# c_Single_Switch_QBC.net
KiCad netlist of a schematic drawn in EAGLE
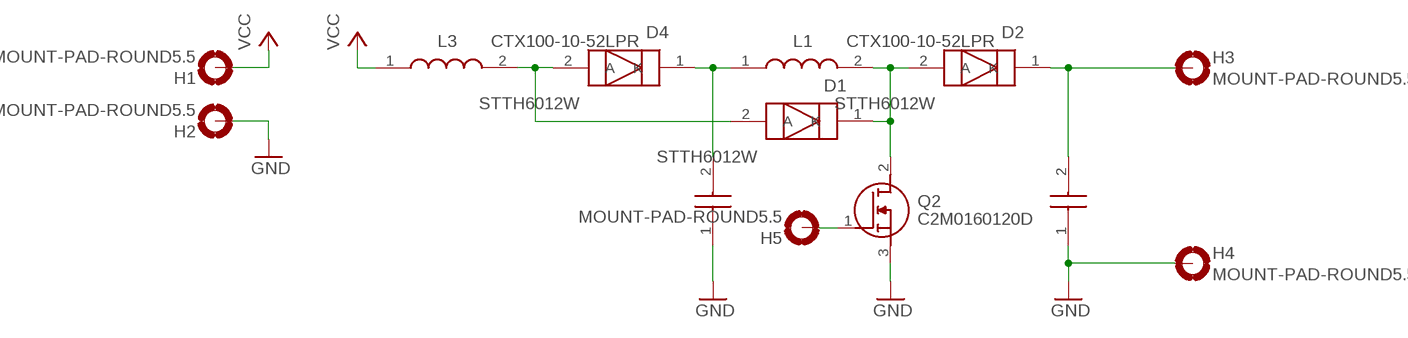
[diagram p0: schematic, sheet 1]

(export (version "E")
  (design (tool "Eeschema 10.0.6"))
  (components
    (comp (ref "D1")
      (value "STTH6012W")
      (footprint "eagle-import:TO1090P515X1560X2445-2P")
      (fields (field (name "RS_PART_NUMBER") "6870818"))
      (libsource (lib "eagle-import") (part "STTH6012W"))
    )
    (comp (ref "D2")
      (value "STTH6012W")
      (footprint "eagle-import:TO1090P515X1560X2445-2P")
      (fields (field (name "RS_PART_NUMBER") "6870818"))
      (libsource (lib "eagle-import") (part "STTH6012W"))
    )
    (comp (ref "D4")
      (value "STTH6012W")
      (footprint "eagle-import:TO1090P515X1560X2445-2P")
      (fields (field (name "RS_PART_NUMBER") "6870818"))
      (libsource (lib "eagle-import") (part "STTH6012W"))
    )
    (comp (ref "H1")
      (value "MOUNT-PAD-ROUND5.5")
      (footprint "eagle-import:5,5-PAD")
      (libsource (lib "eagle-import") (part "MOUNT-PAD-ROUND5.5"))
    )
    (comp (ref "H2")
      (value "MOUNT-PAD-ROUND5.5")
      (footprint "eagle-import:5,5-PAD")
      (libsource (lib "eagle-import") (part "MOUNT-PAD-ROUND5.5"))
    )
    (comp (ref "H3")
      (value "MOUNT-PAD-ROUND5.5")
      (footprint "eagle-import:5,5-PAD")
      (libsource (lib "eagle-import") (part "MOUNT-PAD-ROUND5.5"))
    )
    (comp (ref "H4")
      (value "MOUNT-PAD-ROUND5.5")
      (footprint "eagle-import:5,5-PAD")
      (libsource (lib "eagle-import") (part "MOUNT-PAD-ROUND5.5"))
    )
    (comp (ref "H5")
      (value "MOUNT-PAD-ROUND5.5")
      (footprint "eagle-import:5,5-PAD")
      (libsource (lib "eagle-import") (part "MOUNT-PAD-ROUND5.5"))
    )
    (comp (ref "L1")
      (value "CTX100-10-52LPR")
      (footprint "eagle-import:CTX1001052LPR")
      (libsource (lib "eagle-import") (part "CTX100-10-52LPR"))
    )
    (comp (ref "L3")
      (value "CTX100-10-52LPR")
      (footprint "eagle-import:CTX1001052LPR")
      (libsource (lib "eagle-import") (part "CTX100-10-52LPR"))
    )
    (comp (ref "Q2")
      (value "C2M0160120D")
      (footprint "eagle-import:TO544P521X1594X2550-3P")
      (fields (field (name "RS_PART_NUMBER") "1629709"))
      (libsource (lib "eagle-import") (part "C2M0160120D"))
    )
    (comp (ref "U$1")
      (value "B32774D4505K000")
      (footprint "eagle-import:B32774D4505K000")
      (fields (field (name "RS_PART_NUMBER") "1726009"))
      (libsource (lib "eagle-import") (part "B32774D4505K000"))
    )
    (comp (ref "U$2")
      (value "B32774D4505K000")
      (footprint "eagle-import:B32774D4505K000")
      (fields (field (name "RS_PART_NUMBER") "1726009"))
      (libsource (lib "eagle-import") (part "B32774D4505K000"))
    )
  )
  (nets
    (net (code "1") (name "GND") (class "Default")
      (node (ref "H2") (pin "B5,5") (pinfunction "MOUNT_B5,5") (pintype "passive"))
      (node (ref "H4") (pin "B5,5") (pinfunction "MOUNT_B5,5") (pintype "passive"))
      (node (ref "Q2") (pin "3") (pinfunction "S_3") (pintype "bidirectional"))
      (node (ref "U$1") (pin "1") (pinfunction "1_1") (pintype "bidirectional"))
      (node (ref "U$2") (pin "1") (pinfunction "1_1") (pintype "bidirectional"))
    )
    (net (code "2") (name "Net-(D1-A)") (class "Default")
      (node (ref "D1") (pin "2") (pinfunction "A_2") (pintype "bidirectional"))
      (node (ref "D4") (pin "2") (pinfunction "A_2") (pintype "bidirectional"))
      (node (ref "L3") (pin "2") (pinfunction "2_2") (pintype "bidirectional"))
    )
    (net (code "3") (name "Net-(D1-K)") (class "Default")
      (node (ref "D1") (pin "1") (pinfunction "K_1") (pintype "bidirectional"))
      (node (ref "D2") (pin "2") (pinfunction "A_2") (pintype "bidirectional"))
      (node (ref "L1") (pin "2") (pinfunction "2_2") (pintype "bidirectional"))
      (node (ref "Q2") (pin "2") (pinfunction "D_2") (pintype "bidirectional"))
    )
    (net (code "4") (name "Net-(D2-K)") (class "Default")
      (node (ref "D2") (pin "1") (pinfunction "K_1") (pintype "bidirectional"))
      (node (ref "H3") (pin "B5,5") (pinfunction "MOUNT_B5,5") (pintype "passive"))
      (node (ref "U$2") (pin "2") (pinfunction "2_2") (pintype "bidirectional"))
    )
    (net (code "5") (name "Net-(D4-K)") (class "Default")
      (node (ref "D4") (pin "1") (pinfunction "K_1") (pintype "bidirectional"))
      (node (ref "L1") (pin "1") (pinfunction "1_1") (pintype "bidirectional"))
      (node (ref "U$1") (pin "2") (pinfunction "2_2") (pintype "bidirectional"))
    )
    (net (code "6") (name "Net-(H5-MOUNT)") (class "Default")
      (node (ref "H5") (pin "B5,5") (pinfunction "MOUNT_B5,5") (pintype "passive"))
      (node (ref "Q2") (pin "1") (pinfunction "G_1") (pintype "bidirectional"))
    )
    (net (code "7") (name "VCC") (class "Default")
      (node (ref "H1") (pin "B5,5") (pinfunction "MOUNT_B5,5") (pintype "passive"))
      (node (ref "L3") (pin "1") (pinfunction "1_1") (pintype "bidirectional"))
    )
  )
)
